# BPW21_transimpedance_amplifier.net
KiCad netlist of a schematic drawn in EAGLE
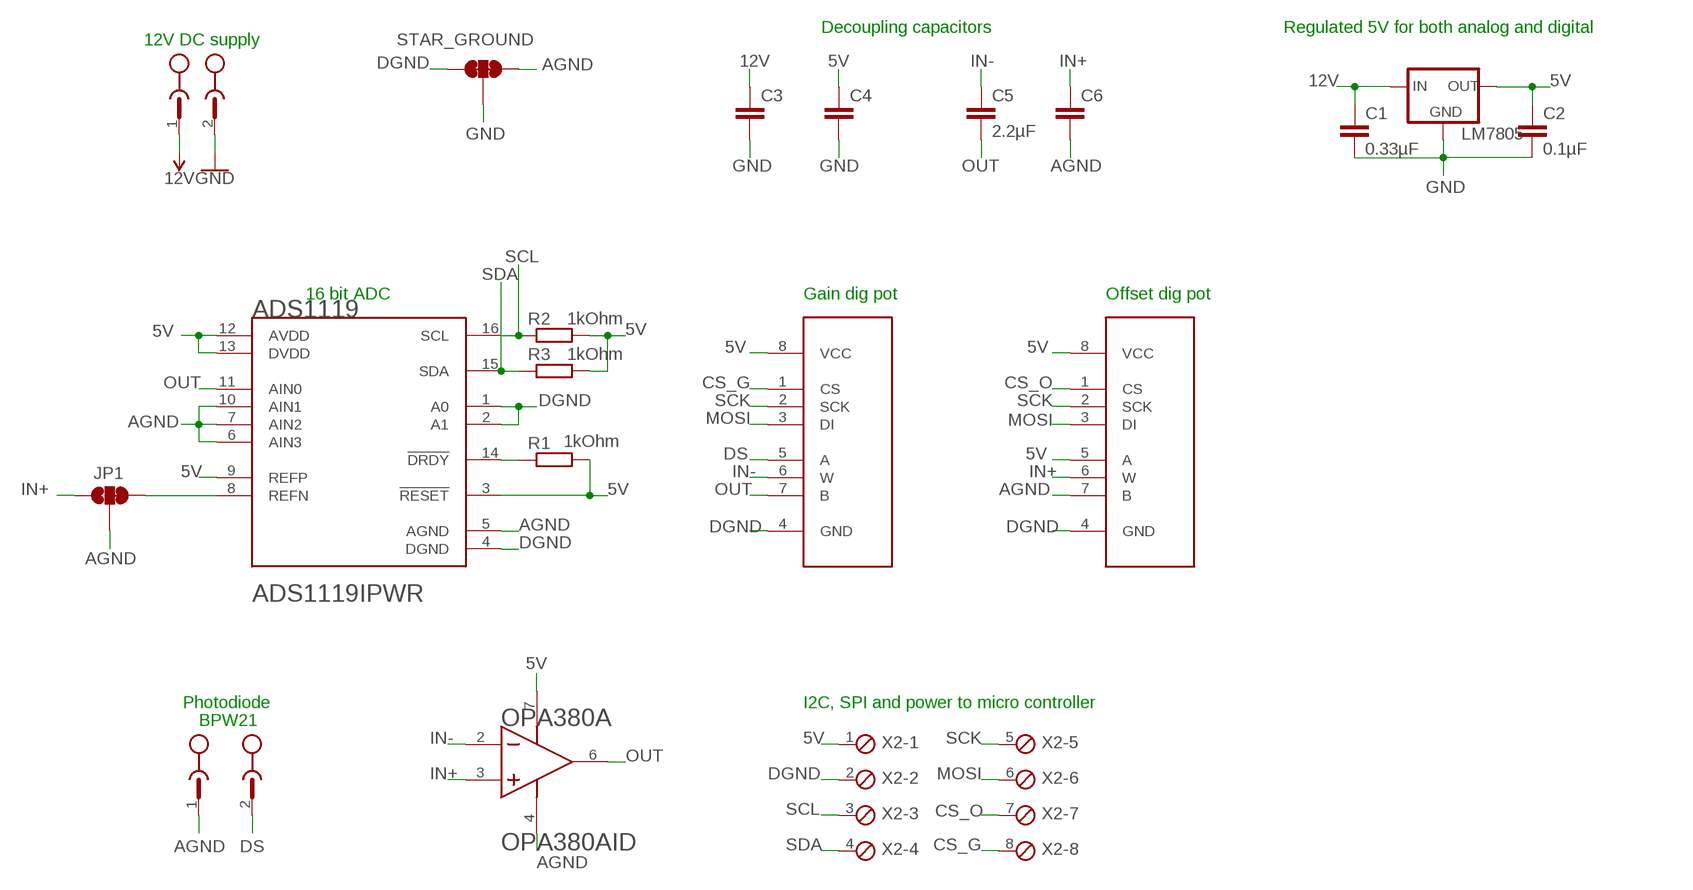
[diagram p0: schematic, sheet 1]

(export (version "E")
  (design (tool "Eeschema 10.0.6"))
  (components
    (comp (ref "ADS1119")
      (value "TEXAS_INSTRUMENTS_ADS1119IPWRTEXAS_INSTRUMENTS_ADS1119IPWR_0_3")
      (footprint "eagle-import:TEXAS_INSTRUMENTS_ADS1119IPWR_3")
      (fields
        (field (name "DIGIKEY_PART_NUMBER") "296-50874-1-ND")
        (field (name "MF") "Texas Instruments")
        (field (name "MOUSER_PART_NUMBER") "595-ADS1119IPWR")
      )
      (libsource (lib "eagle-import") (part "TEXAS_INSTRUMENTS_ADS1119IPWRTEXAS_INSTRUMENTS_ADS1119IPWR_0_3"))
    )
    (comp (ref "BPW21")
      (value "MSTBA2")
      (footprint "eagle-import:MSTBA2")
      (fields (field (name "MF") "FARNELL") (field (name "MPN") "1757242") (field (name "SPICEPREFIX") "X"))
      (libsource (lib "eagle-import") (part "MSTBA2"))
    )
    (comp (ref "C1")
      (value "0.33µF")
      (footprint "eagle-import:C0805")
      (libsource (lib "eagle-import") (part "C-EUC0805"))
    )
    (comp (ref "C2")
      (value "0.1µF")
      (footprint "eagle-import:C0805")
      (libsource (lib "eagle-import") (part "C-EUC0805"))
    )
    (comp (ref "C3")
      (value "C-EUC0805")
      (footprint "eagle-import:C0805")
      (libsource (lib "eagle-import") (part "C-EUC0805"))
    )
    (comp (ref "C4")
      (value "C-EUC0805")
      (footprint "eagle-import:C0805")
      (libsource (lib "eagle-import") (part "C-EUC0805"))
    )
    (comp (ref "C5")
      (value "2.2µF")
      (footprint "eagle-import:C0805")
      (libsource (lib "eagle-import") (part "C-EUC0805"))
    )
    (comp (ref "C6")
      (value "C-EUC0805")
      (footprint "eagle-import:C0805")
      (libsource (lib "eagle-import") (part "C-EUC0805"))
    )
    (comp (ref "GAIN_POT")
      (value "MCP41XXX")
      (footprint "eagle-import:DIP08")
      (libsource (lib "eagle-import") (part "MCP41XXXDIL"))
    )
    (comp (ref "JP1")
      (value "JUMPER-SMT_3_1-NC_TRACE_NO-SILK")
      (footprint "eagle-import:SMT-JUMPER_3_1-NC_TRACE_NO-SILK")
      (libsource (lib "eagle-import") (part "JUMPER-SMT_3_1-NC_TRACE_NO-SILK"))
    )
    (comp (ref "LM7805")
      (value "V_REG_78XX7812")
      (footprint "eagle-import:TO-252")
      (libsource (lib "eagle-import") (part "V_REG_78XX7812"))
    )
    (comp (ref "OFFSET_POT")
      (value "MCP41XXX")
      (footprint "eagle-import:DIP08")
      (libsource (lib "eagle-import") (part "MCP41XXXDIL"))
    )
    (comp (ref "OPA380")
      (value "TEXAS_INSTRUMENTS_OPA380AIDTEXAS_INSTRUMENTS_OPA380AID_0_1")
      (footprint "eagle-import:TEXAS_INSTRUMENTS_OPA380AID_1")
      (fields (field (name "MF") "Texas Instruments") (field (name "MPN") "OPA380AID"))
      (libsource (lib "eagle-import") (part "TEXAS_INSTRUMENTS_OPA380AIDTEXAS_INSTRUMENTS_OPA380AID_0_1"))
    )
    (comp (ref "R1")
      (value "1kOhm")
      (footprint "eagle-import:R0805")
      (libsource (lib "eagle-import") (part "R-EU_R0805"))
    )
    (comp (ref "R2")
      (value "1kOhm")
      (footprint "eagle-import:R0805")
      (libsource (lib "eagle-import") (part "R-EU_R0805"))
    )
    (comp (ref "R3")
      (value "1kOhm")
      (footprint "eagle-import:R0805")
      (libsource (lib "eagle-import") (part "R-EU_R0805"))
    )
    (comp (ref "STAR_GROUND")
      (value "JUMPER-SMT_3_2-NC_TRACE_NO-SILK")
      (footprint "eagle-import:SMT-JUMPER_3_2-NC_TRACE_NO-SILK")
      (libsource (lib "eagle-import") (part "JUMPER-SMT_3_2-NC_TRACE_NO-SILK"))
    )
    (comp (ref "X2")
      (value "MPT8")
      (footprint "eagle-import:8POL254")
      (libsource (lib "eagle-import") (part "MPT8"))
    )
    (comp (ref "X4")
      (value "MSTBA2")
      (footprint "eagle-import:MSTBA2")
      (fields (field (name "MF") "FARNELL") (field (name "MPN") "1757242"))
      (libsource (lib "eagle-import") (part "MSTBA2"))
    )
  )
  (nets
    (net (code "1") (name "/5V") (class "Default")
      (node (ref "ADS1119") (pin "12") (pinfunction "AVDD_12") (pintype "power_in"))
      (node (ref "ADS1119") (pin "13") (pinfunction "DVDD_13") (pintype "power_in"))
      (node (ref "ADS1119") (pin "3") (pinfunction "~{RESET}_3") (pintype "input"))
      (node (ref "ADS1119") (pin "9") (pinfunction "REFP_9") (pintype "passive"))
      (node (ref "C2") (pin "1") (pinfunction "1_1") (pintype "passive"))
      (node (ref "C4") (pin "1") (pinfunction "1_1") (pintype "passive"))
      (node (ref "GAIN_POT") (pin "8") (pinfunction "VCC_8") (pintype "bidirectional"))
      (node (ref "LM7805") (pin "2") (pinfunction "OUT_2") (pintype "passive"))
      (node (ref "OFFSET_POT") (pin "5") (pinfunction "A_5") (pintype "bidirectional"))
      (node (ref "OFFSET_POT") (pin "8") (pinfunction "VCC_8") (pintype "bidirectional"))
      (node (ref "OPA380") (pin "7") (pinfunction "V+_7") (pintype "power_in"))
      (node (ref "R1") (pin "2") (pinfunction "2_2") (pintype "passive"))
      (node (ref "R2") (pin "2") (pinfunction "2_2") (pintype "passive"))
      (node (ref "R3") (pin "2") (pinfunction "2_2") (pintype "passive"))
      (node (ref "X2") (pin "1") (pinfunction "1_1") (pintype "passive"))
    )
    (net (code "2") (name "/AGND") (class "Default")
      (node (ref "ADS1119") (pin "10") (pinfunction "AIN1_10") (pintype "passive"))
      (node (ref "ADS1119") (pin "5") (pinfunction "AGND_5") (pintype "power_in"))
      (node (ref "ADS1119") (pin "6") (pinfunction "AIN3_6") (pintype "passive"))
      (node (ref "ADS1119") (pin "7") (pinfunction "AIN2_7") (pintype "passive"))
      (node (ref "BPW21") (pin "1") (pinfunction "1_1") (pintype "passive"))
      (node (ref "C6") (pin "2") (pinfunction "2_2") (pintype "passive"))
      (node (ref "JP1") (pin "2") (pinfunction "2_2") (pintype "passive"))
      (node (ref "OFFSET_POT") (pin "7") (pinfunction "B_7") (pintype "bidirectional"))
      (node (ref "OPA380") (pin "4") (pinfunction "V-_4") (pintype "power_in"))
      (node (ref "STAR_GROUND") (pin "3") (pinfunction "3_3") (pintype "passive"))
    )
    (net (code "3") (name "/CS_G") (class "Default")
      (node (ref "GAIN_POT") (pin "1") (pinfunction "CS_1") (pintype "bidirectional"))
      (node (ref "X2") (pin "8") (pinfunction "1_8") (pintype "passive"))
    )
    (net (code "4") (name "/CS_O") (class "Default")
      (node (ref "OFFSET_POT") (pin "1") (pinfunction "CS_1") (pintype "bidirectional"))
      (node (ref "X2") (pin "7") (pinfunction "1_7") (pintype "passive"))
    )
    (net (code "5") (name "/DGND") (class "Default")
      (node (ref "ADS1119") (pin "1") (pinfunction "A0_1") (pintype "input"))
      (node (ref "ADS1119") (pin "2") (pinfunction "A1_2") (pintype "input"))
      (node (ref "ADS1119") (pin "4") (pinfunction "DGND_4") (pintype "power_in"))
      (node (ref "GAIN_POT") (pin "4") (pinfunction "GND_4") (pintype "bidirectional"))
      (node (ref "OFFSET_POT") (pin "4") (pinfunction "GND_4") (pintype "bidirectional"))
      (node (ref "STAR_GROUND") (pin "1") (pinfunction "1_1") (pintype "passive"))
      (node (ref "X2") (pin "2") (pinfunction "1_2") (pintype "passive"))
    )
    (net (code "6") (name "/DS") (class "Default")
      (node (ref "BPW21") (pin "2") (pinfunction "1_2") (pintype "passive"))
      (node (ref "GAIN_POT") (pin "5") (pinfunction "A_5") (pintype "bidirectional"))
    )
    (net (code "7") (name "/IN+") (class "Default")
      (node (ref "C6") (pin "1") (pinfunction "1_1") (pintype "passive"))
      (node (ref "JP1") (pin "1") (pinfunction "1_1") (pintype "passive"))
      (node (ref "OFFSET_POT") (pin "6") (pinfunction "W_6") (pintype "bidirectional"))
      (node (ref "OPA380") (pin "3") (pinfunction "IN+_3") (pintype "input"))
    )
    (net (code "8") (name "/IN-") (class "Default")
      (node (ref "C5") (pin "1") (pinfunction "1_1") (pintype "passive"))
      (node (ref "GAIN_POT") (pin "6") (pinfunction "W_6") (pintype "bidirectional"))
      (node (ref "OPA380") (pin "2") (pinfunction "IN-_2") (pintype "input"))
    )
    (net (code "9") (name "/MOSI") (class "Default")
      (node (ref "GAIN_POT") (pin "3") (pinfunction "DI_3") (pintype "bidirectional"))
      (node (ref "OFFSET_POT") (pin "3") (pinfunction "DI_3") (pintype "bidirectional"))
      (node (ref "X2") (pin "6") (pinfunction "1_6") (pintype "passive"))
    )
    (net (code "10") (name "/OUT") (class "Default")
      (node (ref "ADS1119") (pin "11") (pinfunction "AIN0_11") (pintype "passive"))
      (node (ref "C5") (pin "2") (pinfunction "2_2") (pintype "passive"))
      (node (ref "GAIN_POT") (pin "7") (pinfunction "B_7") (pintype "bidirectional"))
      (node (ref "OPA380") (pin "6") (pinfunction "OUT_6") (pintype "output"))
    )
    (net (code "11") (name "/SCK") (class "Default")
      (node (ref "GAIN_POT") (pin "2") (pinfunction "SCK_2") (pintype "bidirectional"))
      (node (ref "OFFSET_POT") (pin "2") (pinfunction "SCK_2") (pintype "bidirectional"))
      (node (ref "X2") (pin "5") (pinfunction "1_5") (pintype "passive"))
    )
    (net (code "12") (name "/SCL") (class "Default")
      (node (ref "ADS1119") (pin "16") (pinfunction "SCL_16") (pintype "input"))
      (node (ref "R2") (pin "1") (pinfunction "1_1") (pintype "passive"))
      (node (ref "X2") (pin "3") (pinfunction "1_3") (pintype "passive"))
    )
    (net (code "13") (name "/SDA") (class "Default")
      (node (ref "ADS1119") (pin "15") (pinfunction "SDA_15") (pintype "bidirectional"))
      (node (ref "R3") (pin "1") (pinfunction "1_1") (pintype "passive"))
      (node (ref "X2") (pin "4") (pinfunction "1_4") (pintype "passive"))
    )
    (net (code "14") (name "12V") (class "Default")
      (node (ref "C1") (pin "1") (pinfunction "1_1") (pintype "passive"))
      (node (ref "C3") (pin "1") (pinfunction "1_1") (pintype "passive"))
      (node (ref "LM7805") (pin "1") (pinfunction "IN_1") (pintype "input"))
      (node (ref "X4") (pin "1") (pinfunction "1_1") (pintype "passive"))
    )
    (net (code "15") (name "GND") (class "Default")
      (node (ref "C1") (pin "2") (pinfunction "2_2") (pintype "passive"))
      (node (ref "C2") (pin "2") (pinfunction "2_2") (pintype "passive"))
      (node (ref "C3") (pin "2") (pinfunction "2_2") (pintype "passive"))
      (node (ref "C4") (pin "2") (pinfunction "2_2") (pintype "passive"))
      (node (ref "LM7805") (pin "3") (pinfunction "GND_3") (pintype "input"))
      (node (ref "STAR_GROUND") (pin "2") (pinfunction "2_2") (pintype "passive"))
      (node (ref "X4") (pin "2") (pinfunction "1_2") (pintype "passive"))
    )
    (net (code "16") (name "Net-(ADS1119-REFN)") (class "Default")
      (node (ref "ADS1119") (pin "8") (pinfunction "REFN_8") (pintype "passive"))
      (node (ref "JP1") (pin "3") (pinfunction "3_3") (pintype "passive"))
    )
    (net (code "17") (name "Net-(ADS1119-~{DRDY})") (class "Default")
      (node (ref "ADS1119") (pin "14") (pinfunction "~{DRDY}_14") (pintype "output"))
      (node (ref "R1") (pin "1") (pinfunction "1_1") (pintype "passive"))
    )
  )
)
